# Common_Drain_Inductor_Balancer.net
KiCad netlist of a schematic drawn in Altium Designer
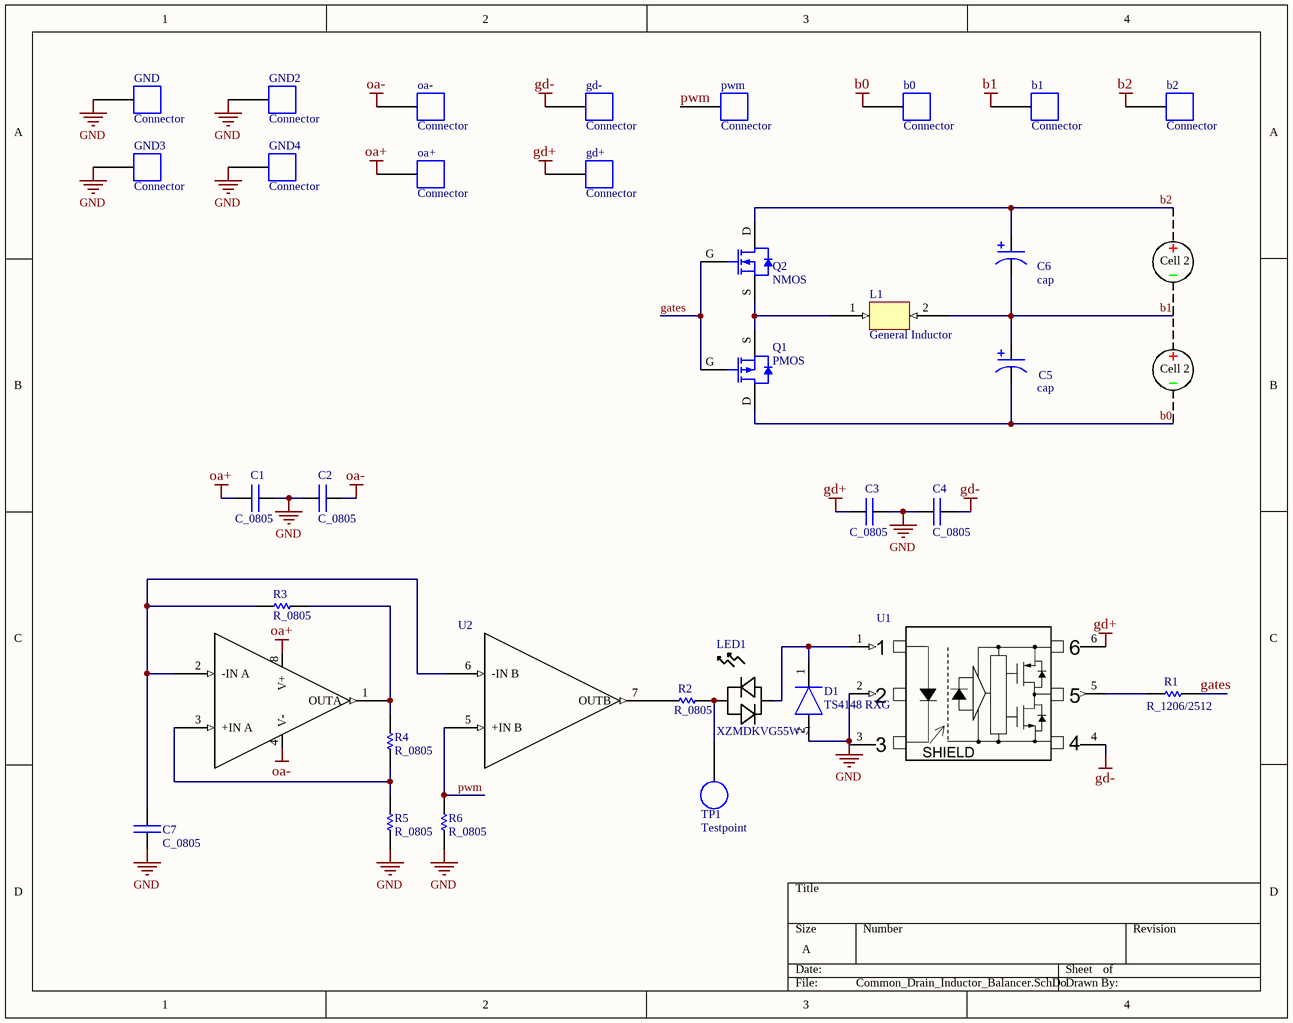
[diagram p0: Common_Drain_Inductor_Balancer.SchDoc]

(export (version "E")
  (design (tool "Eeschema 10.0.6"))
  (components
    (comp (ref "b0")
      (value "Connector")
      (footprint "connector_large")
      (libsource (lib "connector") (part "Connector"))
    )
    (comp (ref "b1")
      (value "Connector")
      (footprint "connector_large")
      (libsource (lib "connector") (part "Connector"))
    )
    (comp (ref "b2")
      (value "Connector")
      (footprint "connector_large")
      (libsource (lib "connector") (part "Connector"))
    )
    (comp (ref "C1") (value "C_0805") (footprint "CAPC2012X14N") (libsource (lib "C_0805") (part "C_0805")))
    (comp (ref "C2") (value "C_0805") (footprint "CAPC2012X14N") (libsource (lib "C_0805") (part "C_0805")))
    (comp (ref "C3") (value "C_0805") (footprint "CAPC2012X14N") (libsource (lib "C_0805") (part "C_0805")))
    (comp (ref "C4") (value "C_0805") (footprint "CAPC2012X14N") (libsource (lib "C_0805") (part "C_0805")))
    (comp (ref "C5") (value "cap") (footprint "cap_by") (libsource (lib "cap") (part "cap")))
    (comp (ref "C6") (value "cap") (footprint "cap_by") (libsource (lib "cap") (part "cap")))
    (comp (ref "C7") (value "C_0805") (footprint "CAPC2012X14N") (libsource (lib "C_0805") (part "C_0805")))
    (comp (ref "D1")
      (value "TS4148 RXG")
      (footprint "DIOC3215X08N")
      (libsource (lib "TS4148 RXG") (part "TS4148 RXG"))
    )
    (comp (ref "gd+")
      (value "Connector")
      (footprint "connector_large")
      (libsource (lib "connector") (part "Connector"))
    )
    (comp (ref "gd-")
      (value "Connector")
      (footprint "connector_large")
      (libsource (lib "connector") (part "Connector"))
    )
    (comp (ref "GND")
      (value "Connector")
      (footprint "connector_large")
      (libsource (lib "connector") (part "Connector"))
    )
    (comp (ref "GND2")
      (value "Connector")
      (footprint "connector_large")
      (libsource (lib "connector") (part "Connector"))
    )
    (comp (ref "GND3")
      (value "Connector")
      (footprint "connector_large")
      (libsource (lib "connector") (part "Connector"))
    )
    (comp (ref "GND4")
      (value "Connector")
      (footprint "connector_large")
      (libsource (lib "connector") (part "Connector"))
    )
    (comp (ref "L1")
      (value "General Inductor")
      (footprint "Inductor_v1")
      (libsource (lib "General_Inductor") (part "General Inductor-Symbol-1"))
    )
    (comp (ref "LED1")
      (value "XZMDKVG55W-7")
      (footprint "DIOC3216X18N")
      (description "No Description Available")
      (fields
        (field (name "MANUFACTURER_PART_NUMBER") "XZMDKVG55W-4")
        (field (name "COPYRIGHT") "Copyright (C) 2018 Accelerated Designs. All rights reserved")
      )
      (libsource (lib "XZMDKVG55W-7") (part "XZMDKVG55W-7"))
    )
    (comp (ref "oa+")
      (value "Connector")
      (footprint "connector_large")
      (libsource (lib "connector") (part "Connector"))
    )
    (comp (ref "oa-")
      (value "Connector")
      (footprint "connector_large")
      (libsource (lib "connector") (part "Connector"))
    )
    (comp (ref "pwm")
      (value "Connector")
      (footprint "connector_large")
      (libsource (lib "connector") (part "Connector"))
    )
    (comp (ref "Q1") (value "PMOS") (footprint "PMOS") (libsource (lib "PMOS") (part "PMOS")))
    (comp (ref "Q2") (value "NMOS") (footprint "NMOS") (libsource (lib "NMOS") (part "NMOS")))
    (comp (ref "R1")
      (value "R_1206/2512")
      (footprint "RESC6331X06N")
      (libsource (lib "R_1206_2512") (part "R_1206/2512"))
    )
    (comp (ref "R2") (value "R_0805") (footprint "RESC2012X06N") (libsource (lib "R_0805") (part "R_0805")))
    (comp (ref "R3") (value "R_0805") (footprint "RESC2012X06N") (libsource (lib "R_0805") (part "R_0805")))
    (comp (ref "R4") (value "R_0805") (footprint "RESC2012X06N") (libsource (lib "R_0805") (part "R_0805")))
    (comp (ref "R5") (value "R_0805") (footprint "RESC2012X06N") (libsource (lib "R_0805") (part "R_0805")))
    (comp (ref "R6") (value "R_0805") (footprint "RESC2012X06N") (libsource (lib "R_0805") (part "R_0805")))
    (comp (ref "TP1")
      (value "Testpoint")
      (footprint "testpoint")
      (libsource (lib "testpoint") (part "Testpoint"))
    )
    (comp (ref "U1")
      (value "TLP5774")
      (footprint "SOIC127P1000X220-6N")
      (libsource (lib "TLP5774") (part "TLP5774"))
    )
    (comp (ref "U2")
      (value "OPA2197")
      (footprint "SOIC127P600X175-8N")
      (libsource (lib "OPA2197") (part "OPA2197"))
    )
  )
  (nets
    (net (code "1") (name "/gates") (class "Default")
      (node (ref "Q1") (pin "G") (pinfunction "G_G") (pintype "passive"))
      (node (ref "Q2") (pin "G") (pinfunction "G_G") (pintype "passive"))
      (node (ref "R1") (pin "2") (pinfunction "2_2") (pintype "passive"))
    )
    (net (code "2") (name "/pwm") (class "Default")
      (node (ref "R6") (pin "2") (pinfunction "2_2") (pintype "passive"))
      (node (ref "U2") (pin "5") (pinfunction "+IN_B_5") (pintype "input"))
      (node (ref "pwm") (pin "1") (pinfunction "1_1") (pintype "passive"))
    )
    (net (code "3") (name "GND") (class "Default")
      (node (ref "C1") (pin "2") (pinfunction "2_2") (pintype "passive"))
      (node (ref "C2") (pin "1") (pinfunction "1_1") (pintype "passive"))
      (node (ref "C3") (pin "2") (pinfunction "2_2") (pintype "passive"))
      (node (ref "C4") (pin "1") (pinfunction "1_1") (pintype "passive"))
      (node (ref "C7") (pin "2") (pinfunction "2_2") (pintype "passive"))
      (node (ref "D1") (pin "2") (pinfunction "A_2") (pintype "passive"))
      (node (ref "GND") (pin "1") (pinfunction "1_1") (pintype "passive"))
      (node (ref "GND2") (pin "1") (pinfunction "1_1") (pintype "passive"))
      (node (ref "GND3") (pin "1") (pinfunction "1_1") (pintype "passive"))
      (node (ref "GND4") (pin "1") (pinfunction "1_1") (pintype "passive"))
      (node (ref "R5") (pin "1") (pinfunction "1_1") (pintype "passive"))
      (node (ref "R6") (pin "1") (pinfunction "1_1") (pintype "passive"))
      (node (ref "U1") (pin "2") (pinfunction "N.C._2") (pintype "input"))
      (node (ref "U1") (pin "3") (pinfunction "Cathode_3") (pintype "power_in"))
    )
    (net (code "4") (name "Net-(D1-C)") (class "Default")
      (node (ref "D1") (pin "1") (pinfunction "C_1") (pintype "passive"))
      (node (ref "LED1") (pin "2") (pinfunction "2_2") (pintype "passive"))
      (node (ref "U1") (pin "1") (pinfunction "Anode_1") (pintype "input"))
    )
    (net (code "5") (name "Net-(L1-Pad1)") (class "Default")
      (node (ref "L1") (pin "1") (pintype "input"))
      (node (ref "Q1") (pin "S") (pinfunction "S_S") (pintype "passive"))
      (node (ref "Q2") (pin "S") (pinfunction "S_S") (pintype "passive"))
    )
    (net (code "6") (name "Net-(LED1-Pad1)") (class "Default")
      (node (ref "LED1") (pin "1") (pinfunction "1_1") (pintype "passive"))
      (node (ref "R2") (pin "2") (pinfunction "2_2") (pintype "passive"))
      (node (ref "TP1") (pin "1") (pinfunction "1_1") (pintype "passive"))
    )
    (net (code "7") (name "Net-(U1-VO)") (class "Default")
      (node (ref "R1") (pin "1") (pinfunction "1_1") (pintype "passive"))
      (node (ref "U1") (pin "5") (pinfunction "VO_5") (pintype "output"))
    )
    (net (code "8") (name "Net-(U2-+IN_A)") (class "Default")
      (node (ref "R4") (pin "2") (pinfunction "2_2") (pintype "passive"))
      (node (ref "R5") (pin "2") (pinfunction "2_2") (pintype "passive"))
      (node (ref "U2") (pin "3") (pinfunction "+IN_A_3") (pintype "input"))
    )
    (net (code "9") (name "Net-(U2--IN_A)") (class "Default")
      (node (ref "C7") (pin "1") (pinfunction "1_1") (pintype "passive"))
      (node (ref "R3") (pin "2") (pinfunction "2_2") (pintype "passive"))
      (node (ref "U2") (pin "2") (pinfunction "-IN_A_2") (pintype "input"))
      (node (ref "U2") (pin "6") (pinfunction "-IN_B_6") (pintype "input"))
    )
    (net (code "10") (name "Net-(U2-OUTA)") (class "Default")
      (node (ref "R3") (pin "1") (pinfunction "1_1") (pintype "passive"))
      (node (ref "R4") (pin "1") (pinfunction "1_1") (pintype "passive"))
      (node (ref "U2") (pin "1") (pinfunction "OUTA_1") (pintype "output"))
    )
    (net (code "11") (name "Net-(U2-OUTB)") (class "Default")
      (node (ref "R2") (pin "1") (pinfunction "1_1") (pintype "passive"))
      (node (ref "U2") (pin "7") (pinfunction "OUTB_7") (pintype "output"))
    )
    (net (code "12") (name "b0") (class "Default")
      (node (ref "C5") (pin "2") (pinfunction "2_2") (pintype "passive"))
      (node (ref "Q1") (pin "D") (pinfunction "D_D") (pintype "passive"))
      (node (ref "b0") (pin "1") (pinfunction "1_1") (pintype "passive"))
    )
    (net (code "13") (name "b1") (class "Default")
      (node (ref "C5") (pin "1") (pinfunction "1_1") (pintype "passive"))
      (node (ref "C6") (pin "2") (pinfunction "2_2") (pintype "passive"))
      (node (ref "L1") (pin "2") (pintype "input"))
      (node (ref "b1") (pin "1") (pinfunction "1_1") (pintype "passive"))
    )
    (net (code "14") (name "b2") (class "Default")
      (node (ref "C6") (pin "1") (pinfunction "1_1") (pintype "passive"))
      (node (ref "Q2") (pin "D") (pinfunction "D_D") (pintype "passive"))
      (node (ref "b2") (pin "1") (pinfunction "1_1") (pintype "passive"))
    )
    (net (code "15") (name "gd+") (class "Default")
      (node (ref "C3") (pin "1") (pinfunction "1_1") (pintype "passive"))
      (node (ref "U1") (pin "6") (pinfunction "VCC_6") (pintype "power_in"))
      (node (ref "gd+") (pin "1") (pinfunction "1_1") (pintype "passive"))
    )
    (net (code "16") (name "gd-") (class "Default")
      (node (ref "C4") (pin "2") (pinfunction "2_2") (pintype "passive"))
      (node (ref "U1") (pin "4") (pinfunction "GND_4") (pintype "power_in"))
      (node (ref "gd-") (pin "1") (pinfunction "1_1") (pintype "passive"))
    )
    (net (code "17") (name "oa+") (class "Default")
      (node (ref "C1") (pin "1") (pinfunction "1_1") (pintype "passive"))
      (node (ref "U2") (pin "8") (pinfunction "V+_8") (pintype "power_in"))
      (node (ref "oa+") (pin "1") (pinfunction "1_1") (pintype "passive"))
    )
    (net (code "18") (name "oa-") (class "Default")
      (node (ref "C2") (pin "2") (pinfunction "2_2") (pintype "passive"))
      (node (ref "U2") (pin "4") (pinfunction "V-_4") (pintype "power_in"))
      (node (ref "oa-") (pin "1") (pinfunction "1_1") (pintype "passive"))
    )
  )
)
